# GPS.net
KiCad netlist of a schematic drawn in Altium Designer
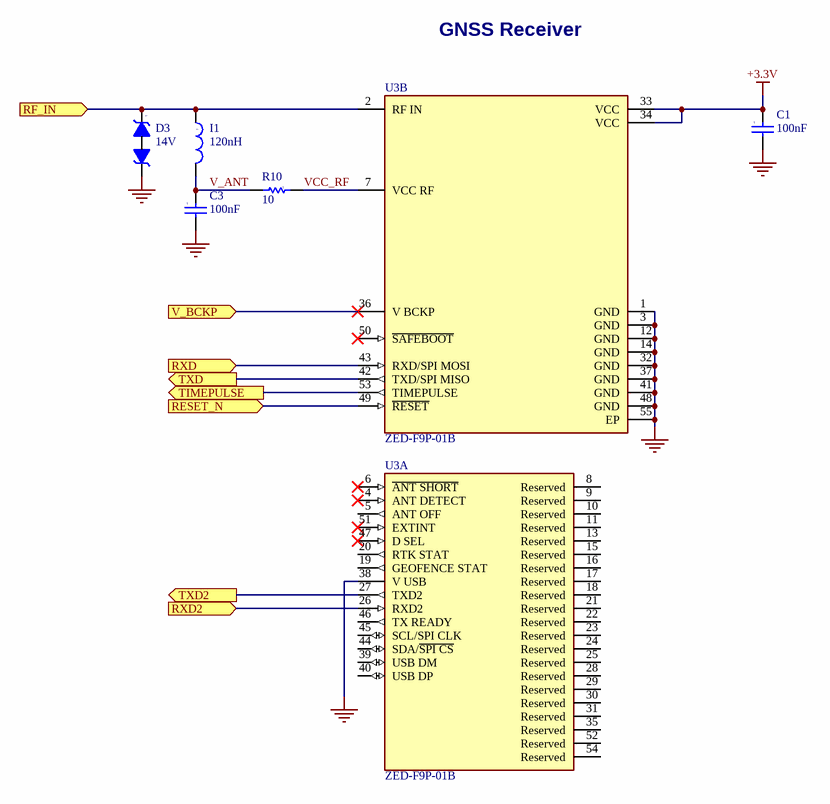
[diagram p0: GPS.SchDoc]

(export (version "E")
  (design (tool "Eeschema 10.0.6"))
  (components
    (comp (ref "C1")
      (value "100nF")
      (footprint "0402")
      (description "CAP CER .10UF 50V X7R 10% 0402")
      (fields
        (field (name "MANUFACTURER") "TDK Corporation")
        (field (name "MANUFACTURER PART NUMBER") "C1005X7R1H104K")
        (field (name "PUBLISHER") "Altium Limited")
      )
      (libsource (lib "General") (part "Cap"))
    )
    (comp (ref "C3")
      (value "100nF")
      (footprint "0402")
      (description "CAP CER .10UF 50V X7R 10% 0402")
      (fields
        (field (name "MANUFACTURER") "TDK Corporation")
        (field (name "MANUFACTURER PART NUMBER") "C1005X7R1H104K")
        (field (name "PUBLISHER") "Altium Limited")
      )
      (libsource (lib "General") (part "Cap"))
    )
    (comp (ref "D3")
      (value "Diode - Bidirectional Zener")
      (footprint "R0402")
      (description "LITTELFUSE - PESD0402-140 - DIODE, ESD PROTECTION, 0402, FULL REEL")
      (fields
        (field (name "MANUFACTURER") "Littelfuse")
        (field (name "MANUFACTURER PART NUMBER") "PESD0402-140")
        (field (name "WORKING VOLTAGE") "14V")
      )
      (libsource (lib "General") (part "Diode - Bidirectional Zener"))
    )
    (comp (ref "I1")
      (value "120nH")
      (footprint "0402")
      (description "Inductor RF Chip Wirewound 120nH 5% 100MHz 20Q-Factor 110mA 2.66Ohm DCR 0402 Paper T/R")
      (fields
        (field (name "MANUFACTURER") "Murata")
        (field (name "MANUFACTURER PART NUMBER") "LQW15ANR12J00D")
      )
      (libsource (lib "General") (part "Inductor"))
    )
    (comp (ref "R10")
      (value "10")
      (footprint "R0402")
      (description "RES SMD 10 OHM 5% 1/5W 0402")
      (fields
        (field (name "MANUFACTURER") "Rohm Semiconductor")
        (field (name "MANUFACTURER PART NUMBER") "ESR01MZPJ100")
      )
      (libsource (lib "General") (part "Res"))
    )
    (comp (ref "U3")
      (value "ZED-F9P-01B")
      (footprint "U-Blox_ZED-F9P")
      (fields (field (name "MANUFACTURER") "u-blox") (field (name "MANUFACTURER PART NUMBER") "ZED-F9P-01B"))
      (libsource (lib "Wagstaff") (part "U-Blox_ZED-F9P-01B_Client(IS)"))
    )
  )
  (nets
    (net (code "1") (name "+3.3V") (class "Default")
      (node (ref "C1") (pin "1") (pinfunction "1_1") (pintype "passive"))
      (node (ref "U3") (pin "33") (pinfunction "VCC_33") (pintype "power_in"))
      (node (ref "U3") (pin "34") (pinfunction "VCC_34") (pintype "power_in"))
    )
    (net (code "2") (name "/RESET_N") (class "Default")
      (node (ref "U3") (pin "49") (pinfunction "~{RESET}_49") (pintype "input"))
    )
    (net (code "3") (name "/RF_IN") (class "Default")
      (node (ref "D3") (pin "1") (pinfunction "1_1") (pintype "passive"))
      (node (ref "I1") (pin "1") (pinfunction "1_1") (pintype "passive"))
      (node (ref "U3") (pin "2") (pinfunction "RF_IN_2") (pintype "passive"))
    )
    (net (code "4") (name "/RXD") (class "Default")
      (node (ref "U3") (pin "43") (pinfunction "RXD/SPI_MOSI_43") (pintype "input"))
    )
    (net (code "5") (name "/RXD2") (class "Default")
      (node (ref "U3") (pin "26") (pinfunction "RXD2_26") (pintype "input"))
    )
    (net (code "6") (name "/TIMEPULSE") (class "Default")
      (node (ref "U3") (pin "53") (pinfunction "TIMEPULSE_53") (pintype "output"))
    )
    (net (code "7") (name "/TXD") (class "Default")
      (node (ref "U3") (pin "42") (pinfunction "TXD/SPI_MISO_42") (pintype "output"))
    )
    (net (code "8") (name "/TXD2") (class "Default")
      (node (ref "U3") (pin "27") (pinfunction "TXD2_27") (pintype "output"))
    )
    (net (code "9") (name "/VCC_RF") (class "Default")
      (node (ref "R10") (pin "1") (pinfunction "1_1") (pintype "passive"))
      (node (ref "U3") (pin "7") (pinfunction "VCC_RF_7") (pintype "power_in"))
    )
    (net (code "10") (name "/V_ANT") (class "Default")
      (node (ref "C3") (pin "1") (pinfunction "1_1") (pintype "passive"))
      (node (ref "I1") (pin "2") (pinfunction "2_2") (pintype "passive"))
      (node (ref "R10") (pin "2") (pinfunction "2_2") (pintype "passive"))
    )
    (net (code "11") (name "/V_BCKP") (class "Default")
      (node (ref "U3") (pin "36") (pinfunction "V_BCKP_36") (pintype "power_in+no_connect"))
    )
    (net (code "12") (name "GND") (class "Default")
      (node (ref "C1") (pin "2") (pinfunction "2_2") (pintype "passive"))
      (node (ref "C3") (pin "2") (pinfunction "2_2") (pintype "passive"))
      (node (ref "D3") (pin "2") (pinfunction "2_2") (pintype "passive"))
      (node (ref "U3") (pin "1") (pinfunction "GND_1") (pintype "power_in"))
      (node (ref "U3") (pin "12") (pinfunction "GND_12") (pintype "power_in"))
      (node (ref "U3") (pin "14") (pinfunction "GND_14") (pintype "power_in"))
      (node (ref "U3") (pin "3") (pinfunction "GND_3") (pintype "power_in"))
      (node (ref "U3") (pin "32") (pinfunction "GND_32") (pintype "power_in"))
      (node (ref "U3") (pin "37") (pinfunction "GND_37") (pintype "power_in"))
      (node (ref "U3") (pin "38") (pinfunction "V_USB_38") (pintype "power_in"))
      (node (ref "U3") (pin "41") (pinfunction "GND_41") (pintype "power_in"))
      (node (ref "U3") (pin "48") (pinfunction "GND_48") (pintype "power_in"))
      (node (ref "U3") (pin "55") (pinfunction "EP_55") (pintype "power_in"))
    )
    (net (code "13") (name "unconnected-(U3A-ANT_DETECT-Pad4)") (class "Default")
      (node (ref "U3") (pin "4") (pinfunction "ANT_DETECT_4") (pintype "input+no_connect"))
    )
    (net (code "14") (name "unconnected-(U3A-ANT_OFF-Pad5)") (class "Default")
      (node (ref "U3") (pin "5") (pinfunction "ANT_OFF_5") (pintype "output"))
    )
    (net (code "15") (name "unconnected-(U3A-D_SEL-Pad47)") (class "Default")
      (node (ref "U3") (pin "47") (pinfunction "D_SEL_47") (pintype "input+no_connect"))
    )
    (net (code "16") (name "unconnected-(U3A-EXTINT-Pad51)") (class "Default")
      (node (ref "U3") (pin "51") (pinfunction "EXTINT_51") (pintype "input+no_connect"))
    )
    (net (code "17") (name "unconnected-(U3A-GEOFENCE_STAT-Pad19)") (class "Default")
      (node (ref "U3") (pin "19") (pinfunction "GEOFENCE_STAT_19") (pintype "output"))
    )
    (net (code "18") (name "unconnected-(U3A-RTK_STAT-Pad20)") (class "Default")
      (node (ref "U3") (pin "20") (pinfunction "RTK_STAT_20") (pintype "output"))
    )
    (net (code "19") (name "unconnected-(U3A-Reserved-Pad8)") (class "Default")
      (node (ref "U3") (pin "8") (pinfunction "Reserved_8") (pintype "passive"))
    )
    (net (code "20") (name "unconnected-(U3A-Reserved-Pad9)") (class "Default")
      (node (ref "U3") (pin "9") (pinfunction "Reserved_9") (pintype "passive"))
    )
    (net (code "21") (name "unconnected-(U3A-Reserved-Pad10)") (class "Default")
      (node (ref "U3") (pin "10") (pinfunction "Reserved_10") (pintype "passive"))
    )
    (net (code "22") (name "unconnected-(U3A-Reserved-Pad11)") (class "Default")
      (node (ref "U3") (pin "11") (pinfunction "Reserved_11") (pintype "passive"))
    )
    (net (code "23") (name "unconnected-(U3A-Reserved-Pad13)") (class "Default")
      (node (ref "U3") (pin "13") (pinfunction "Reserved_13") (pintype "passive"))
    )
    (net (code "24") (name "unconnected-(U3A-Reserved-Pad15)") (class "Default")
      (node (ref "U3") (pin "15") (pinfunction "Reserved_15") (pintype "passive"))
    )
    (net (code "25") (name "unconnected-(U3A-Reserved-Pad16)") (class "Default")
      (node (ref "U3") (pin "16") (pinfunction "Reserved_16") (pintype "passive"))
    )
    (net (code "26") (name "unconnected-(U3A-Reserved-Pad17)") (class "Default")
      (node (ref "U3") (pin "17") (pinfunction "Reserved_17") (pintype "passive"))
    )
    (net (code "27") (name "unconnected-(U3A-Reserved-Pad18)") (class "Default")
      (node (ref "U3") (pin "18") (pinfunction "Reserved_18") (pintype "passive"))
    )
    (net (code "28") (name "unconnected-(U3A-Reserved-Pad21)") (class "Default")
      (node (ref "U3") (pin "21") (pinfunction "Reserved_21") (pintype "passive"))
    )
    (net (code "29") (name "unconnected-(U3A-Reserved-Pad22)") (class "Default")
      (node (ref "U3") (pin "22") (pinfunction "Reserved_22") (pintype "passive"))
    )
    (net (code "30") (name "unconnected-(U3A-Reserved-Pad23)") (class "Default")
      (node (ref "U3") (pin "23") (pinfunction "Reserved_23") (pintype "passive"))
    )
    (net (code "31") (name "unconnected-(U3A-Reserved-Pad24)") (class "Default")
      (node (ref "U3") (pin "24") (pinfunction "Reserved_24") (pintype "passive"))
    )
    (net (code "32") (name "unconnected-(U3A-Reserved-Pad25)") (class "Default")
      (node (ref "U3") (pin "25") (pinfunction "Reserved_25") (pintype "passive"))
    )
    (net (code "33") (name "unconnected-(U3A-Reserved-Pad28)") (class "Default")
      (node (ref "U3") (pin "28") (pinfunction "Reserved_28") (pintype "passive"))
    )
    (net (code "34") (name "unconnected-(U3A-Reserved-Pad29)") (class "Default")
      (node (ref "U3") (pin "29") (pinfunction "Reserved_29") (pintype "passive"))
    )
    (net (code "35") (name "unconnected-(U3A-Reserved-Pad30)") (class "Default")
      (node (ref "U3") (pin "30") (pinfunction "Reserved_30") (pintype "passive"))
    )
    (net (code "36") (name "unconnected-(U3A-Reserved-Pad31)") (class "Default")
      (node (ref "U3") (pin "31") (pinfunction "Reserved_31") (pintype "passive"))
    )
    (net (code "37") (name "unconnected-(U3A-Reserved-Pad35)") (class "Default")
      (node (ref "U3") (pin "35") (pinfunction "Reserved_35") (pintype "passive"))
    )
    (net (code "38") (name "unconnected-(U3A-Reserved-Pad52)") (class "Default")
      (node (ref "U3") (pin "52") (pinfunction "Reserved_52") (pintype "passive"))
    )
    (net (code "39") (name "unconnected-(U3A-Reserved-Pad54)") (class "Default")
      (node (ref "U3") (pin "54") (pinfunction "Reserved_54") (pintype "passive"))
    )
    (net (code "40") (name "unconnected-(U3A-SCL{slash}SPI_CLK-Pad45)") (class "Default")
      (node (ref "U3") (pin "45") (pinfunction "SCL/SPI_CLK_45") (pintype "bidirectional"))
    )
    (net (code "41") (name "unconnected-(U3A-SDA{slash}~{SPI_CS}-Pad44)") (class "Default")
      (node (ref "U3") (pin "44") (pinfunction "SDA/~{SPI_CS}_44") (pintype "bidirectional"))
    )
    (net (code "42") (name "unconnected-(U3A-TX_READY-Pad46)") (class "Default")
      (node (ref "U3") (pin "46") (pinfunction "TX_READY_46") (pintype "output"))
    )
    (net (code "43") (name "unconnected-(U3A-USB_DM-Pad39)") (class "Default")
      (node (ref "U3") (pin "39") (pinfunction "USB_DM_39") (pintype "bidirectional"))
    )
    (net (code "44") (name "unconnected-(U3A-USB_DP-Pad40)") (class "Default")
      (node (ref "U3") (pin "40") (pinfunction "USB_DP_40") (pintype "bidirectional"))
    )
    (net (code "45") (name "unconnected-(U3A-~{ANT_SHORT}-Pad6)") (class "Default")
      (node (ref "U3") (pin "6") (pinfunction "~{ANT_SHORT}_6") (pintype "input+no_connect"))
    )
    (net (code "46") (name "unconnected-(U3B-~{SAFEBOOT}-Pad50)") (class "Default")
      (node (ref "U3") (pin "50") (pinfunction "~{SAFEBOOT}_50") (pintype "input+no_connect"))
    )
  )
)
